# ESP32_FLASH_CARD_READER.net
KiCad netlist of a schematic drawn in Altium Designer
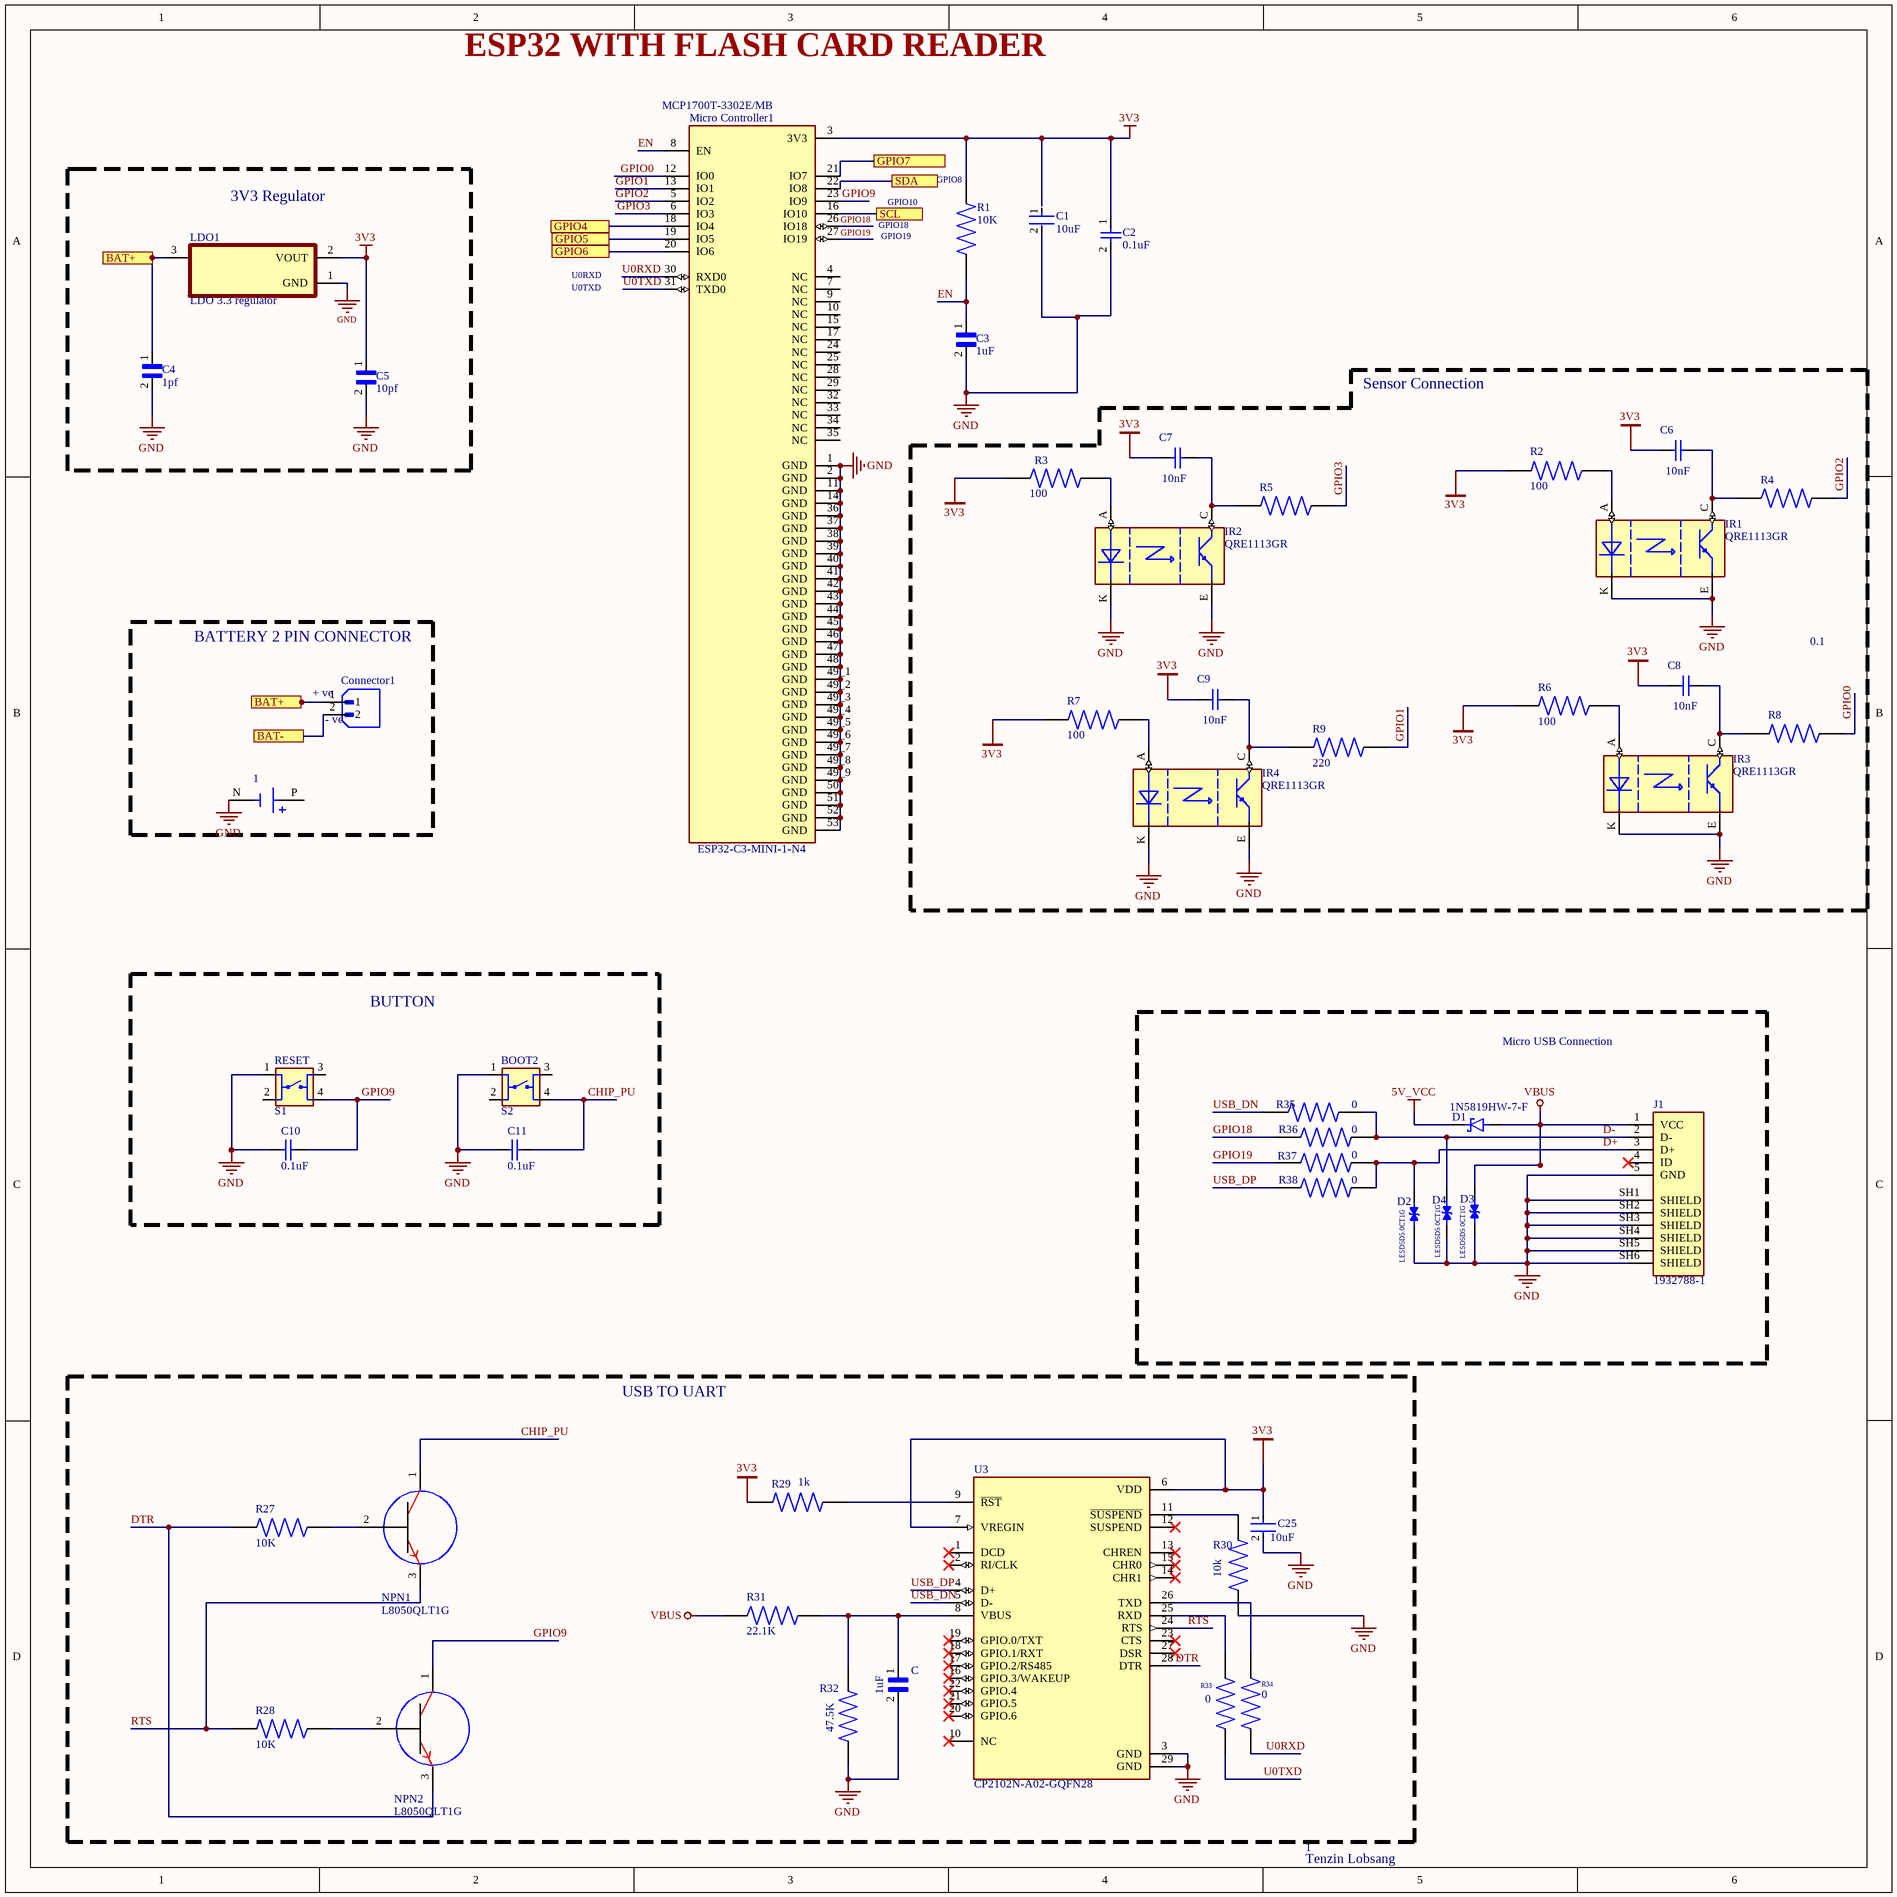
[diagram p0: ESP32_FLASH_CARD_READER.SchDoc]

(export (version "E")
  (design (tool "Eeschema 10.0.6"))
  (components
    (comp (ref "1")
      (value "~")
      (footprint "BAT_1043")
      (fields (field (name "MP") "1043"))
      (libsource (lib "1043") (part "1043"))
    )
    (comp (ref "BOOT2")
      (value "S2")
      (footprint "SW_4-1437565-2")
      (description "Switch Tactile OFF (ON) SPST Round Button Gull Wing 0.05A 12VDC 1.57N SMD T/R")
      (fields (field (name "MP") "4-1437565-2"))
      (libsource (lib "Switch_button") (part "4-1437565-2"))
    )
    (comp (ref "C")
      (value "1uF")
      (footprint "CAPC1608X90N")
      (description "1ÂµF Â±10% 16V Ceramic Capacitor X7R 0603 (1608 Metric)")
      (fields (field (name "DIGI-KEY_PART_NUMBER") "1276-1019-1-ND") (field (name "MP") "CL10B105KO8NNNC"))
      (libsource (lib "CAP_1uF") (part "CL10B105KO8NNNC"))
    )
    (comp (ref "C1")
      (value "10uF")
      (footprint "CAPC2012X88N")
      (description "Cap Ceramic 10uF 25V X5R ±20% Pad SMD 0603 +85°C T/R")
      (fields (field (name "TOLERANCE") "20%"))
      (libsource (lib "CAP 10 uF") (part "CMP-13271-004224-1"))
    )
    (comp (ref "C2")
      (value "0.1uF")
      (footprint "CAPC1608X90X35NL10T15")
      (description "Chip Capacitor, 0.1 uF, +/- 10%, 50 V, -55 to 125 degC, 0603 (1608 Metric), RoHS, Tape and Reel")
      (fields (field (name "TOLERANCE") "10%") (field (name "VOLTAGE") "50V"))
      (libsource (lib "") (part "CMP-2100-03643-1_1"))
    )
    (comp (ref "C3")
      (value "1uF")
      (footprint "CAPC1608X90N")
      (description "1ÂµF Â±10% 16V Ceramic Capacitor X7R 0603 (1608 Metric)")
      (fields (field (name "DIGI-KEY_PART_NUMBER") "1276-1019-1-ND") (field (name "MP") "CL10B105KO8NNNC"))
      (libsource (lib "CAP_1uF") (part "CL10B105KO8NNNC"))
    )
    (comp (ref "C4")
      (value "1pf")
      (footprint "CAPC2012X88N")
      (fields (field (name "MP") "C0805C100K5RAC7800"))
      (libsource (lib "C0805C100K5RAC7800") (part "C0805C100K5RAC7800"))
    )
    (comp (ref "C5")
      (value "10pf")
      (footprint "CAPC2012X88N")
      (fields (field (name "MP") "C0805C100K5RAC7800"))
      (libsource (lib "C0805C100K5RAC7800") (part "C0805C100K5RAC7800"))
    )
    (comp (ref "C6")
      (value "10nF")
      (footprint "WCAP-CSGP_0805_L2W1.25H1.25")
      (description "WCAP-CSGP Multilayer Ceramic Chip Capacitor, General Purpose, size 0805, NP0, 10nF, 10V")
      (fields
        (field (name "MANUFACTURER PART NUMBER") "885012007009")
        (field (name "MANUFACTURER") "Wurth Elektronik")
      )
      (libsource (lib "10nf_CAP_WCAP-CSGP") (part "885012007009"))
    )
    (comp (ref "C7")
      (value "10nF")
      (footprint "WCAP-CSGP_0805_L2W1.25H1.25")
      (description "WCAP-CSGP Multilayer Ceramic Chip Capacitor, General Purpose, size 0805, NP0, 10nF, 10V")
      (fields
        (field (name "MANUFACTURER PART NUMBER") "885012007009")
        (field (name "MANUFACTURER") "Wurth Elektronik")
      )
      (libsource (lib "10nf_CAP_WCAP-CSGP") (part "885012007009"))
    )
    (comp (ref "C8")
      (value "10nF")
      (footprint "WCAP-CSGP_0805_L2W1.25H1.25")
      (description "WCAP-CSGP Multilayer Ceramic Chip Capacitor, General Purpose, size 0805, NP0, 10nF, 10V")
      (fields
        (field (name "MANUFACTURER PART NUMBER") "885012007009")
        (field (name "MANUFACTURER") "Wurth Elektronik")
      )
      (libsource (lib "10nf_CAP_WCAP-CSGP") (part "885012007009"))
    )
    (comp (ref "C9")
      (value "10nF")
      (footprint "WCAP-CSGP_0805_L2W1.25H1.25")
      (description "WCAP-CSGP Multilayer Ceramic Chip Capacitor, General Purpose, size 0805, NP0, 10nF, 10V")
      (fields
        (field (name "MANUFACTURER PART NUMBER") "885012007009")
        (field (name "MANUFACTURER") "Wurth Elektronik")
      )
      (libsource (lib "10nf_CAP_WCAP-CSGP") (part "885012007009"))
    )
    (comp (ref "C10")
      (value "0.1uF")
      (footprint "CAPC1608X90X35NL10T15")
      (description "Chip Capacitor, 0.1 uF, +/- 10%, 50 V, -55 to 125 degC, 0603 (1608 Metric), RoHS, Tape and Reel")
      (fields (field (name "TOLERANCE") "10%") (field (name "VOLTAGE") "50V"))
      (libsource (lib "CAP 0.1uF") (part "CMP-2100-03643-1"))
    )
    (comp (ref "C11")
      (value "0.1uF")
      (footprint "CAPC1608X90X35NL10T15")
      (description "Chip Capacitor, 0.1 uF, +/- 10%, 50 V, -55 to 125 degC, 0603 (1608 Metric), RoHS, Tape and Reel")
      (fields (field (name "TOLERANCE") "10%") (field (name "VOLTAGE") "50V"))
      (libsource (lib "CAP 0.1uF") (part "CMP-2100-03643-1"))
    )
    (comp (ref "C25")
      (value "10uF")
      (footprint "CAPC2012X88N")
      (description "Cap Ceramic 10uF 25V X5R ±20% Pad SMD 0603 +85°C T/R")
      (fields (field (name "TOLERANCE") "20%"))
      (libsource (lib "CAP 10 uF") (part "CMP-13271-004224-1"))
    )
    (comp (ref "Connector1")
      (value "B2B-XH-A")
      (footprint "JST_B2B-XH-A")
      (fields (field (name "MF") "{'manufacturer': u'JST Sales America Inc.'}"))
      (libsource (lib "2_pin_connector_B2B-XH-A") (part "B2B-XH-A"))
    )
    (comp (ref "D1")
      (value "1N5819HW-7-F")
      (footprint "SOD3715X145N")
      (description "Diode Schottky 40 V 1A Surface Mount SOD-123")
      (fields (field (name "MF") "Diodes Inc."))
      (libsource (lib "D1_1N589HW-7-F") (part "1N5819HW-7-F"))
    )
    (comp (ref "D2")
      (value "LESD5D5.0CT1G")
      (footprint "TVS_LESD5D5.0CT1G")
      (description "Transient Voltage Suppressors for ESD Protection")
      (fields (field (name "MF") "Leshan Radio Co."))
      (libsource (lib "D2_LESD5_OCTR1G") (part "LESD5D5.0CT1G"))
    )
    (comp (ref "D3")
      (value "LESD5D5.0CT1G")
      (footprint "TVS_LESD5D5.0CT1G")
      (description "Transient Voltage Suppressors for ESD Protection")
      (fields (field (name "MF") "Leshan Radio Co."))
      (libsource (lib "D2_LESD5_OCTR1G") (part "LESD5D5.0CT1G"))
    )
    (comp (ref "D4")
      (value "LESD5D5.0CT1G")
      (footprint "TVS_LESD5D5.0CT1G")
      (description "Transient Voltage Suppressors for ESD Protection")
      (fields (field (name "MF") "Leshan Radio Co."))
      (libsource (lib "D2_LESD5_OCTR1G") (part "LESD5D5.0CT1G"))
    )
    (comp (ref "IR1")
      (value "QRE1113GR")
      (footprint "4LEADSMD")
      (description "Optical Switches, Reflective, Phototransistor Output Reflective Sensor")
      (fields (field (name "MF") "SparkFun") (field (name "MP") "QRE1113"))
      (libsource (lib "QRE1113GR") (part "QRE1113GR"))
    )
    (comp (ref "IR2")
      (value "QRE1113GR")
      (footprint "4LEADSMD")
      (description "Optical Switches, Reflective, Phototransistor Output Reflective Sensor")
      (fields (field (name "MF") "SparkFun") (field (name "MP") "QRE1113"))
      (libsource (lib "QRE1113GR") (part "QRE1113GR"))
    )
    (comp (ref "IR3")
      (value "QRE1113GR")
      (footprint "4LEADSMD")
      (description "Optical Switches, Reflective, Phototransistor Output Reflective Sensor")
      (fields (field (name "MF") "SparkFun") (field (name "MP") "QRE1113"))
      (libsource (lib "QRE1113GR") (part "QRE1113GR"))
    )
    (comp (ref "IR4")
      (value "QRE1113GR")
      (footprint "4LEADSMD")
      (description "Optical Switches, Reflective, Phototransistor Output Reflective Sensor")
      (fields (field (name "MF") "SparkFun") (field (name "MP") "QRE1113"))
      (libsource (lib "QRE1113GR") (part "QRE1113GR"))
    )
    (comp (ref "J1")
      (value "1932788-1")
      (footprint "TE_1932788-1")
      (libsource (lib "Micro_USB") (part "1932788-1"))
    )
    (comp (ref "LDO1")
      (value "LDO 3.3 regulator")
      (footprint "SOT95P237X112-3N")
      (description "25V 10uF X5R ±20% 0603 Multilayer Ceramic Capacitors MLCC - SMD/SMT ROHS")
      (fields (field (name "MP") "MCP1700T-3002E/TT") (field (name "MF") "Microchip"))
      (libsource (lib "Flash_Card_Reader_1") (part "MCP1700T-3002E/TT"))
    )
    (comp (ref "Micro Controller1")
      (value "ESP32-C3-MINI-1-N4")
      (footprint "XCVR_ESP32-C3-MINI-1-N4")
      (description "Pwr Sply Func, Voltage Regulator, LDO, SOT-89, PD 1.635W, VO 3.3V, Regline +/-0.75%/V")
      (fields
        (field (name "MF") "Espressif Systems")
        (field (name "SUPPLIER PART NUMBER 1") "MCP1700T-3302E/MB")
        (field (name "MANUFACTURER") "Microchip")
      )
      (libsource (lib "ESP32-C3-MINI-1-N4") (part "ESP32-C3-MINI-1-N4"))
    )
    (comp (ref "NPN1")
      (value "L8050QLT1G")
      (footprint "SOT-23")
      (libsource (lib "Transistor") (part "L8050QLT1G"))
    )
    (comp (ref "NPN2")
      (value "L8050QLT1G")
      (footprint "SOT-23")
      (libsource (lib "Transistor") (part "L8050QLT1G"))
    )
    (comp (ref "R1")
      (value "10K")
      (footprint "RESC1005X40N")
      (description "CRG0402 chip resistor,10K 5% 0.063W ¦ TE Connectivity CRG0402J10K/10")
      (fields (field (name "MF") "TE Connectivity") (field (name "MP") "CRG0402J10K/10"))
      (libsource (lib "10K_CRG0402J10K_10") (part "CRG0402J10K/10"))
    )
    (comp (ref "R2")
      (value "100")
      (footprint "RESC6432X75N")
      (description "CRS Series Anti-surge Resistor 2512 Case 100Ohms 2W +/-100ppm/degC ¦ Bourns CRS2512-FX-1000ELF")
      (fields (field (name "MF") "Bourns") (field (name "MP") "CRS2512-FX-1000ELF"))
      (libsource (lib "100ohh") (part "CRS2512-FX-1000ELF"))
    )
    (comp (ref "R3")
      (value "100")
      (footprint "RESC6432X75N")
      (description "CRS Series Anti-surge Resistor 2512 Case 100Ohms 2W +/-100ppm/degC ¦ Bourns CRS2512-FX-1000ELF")
      (fields (field (name "MF") "Bourns") (field (name "MP") "CRS2512-FX-1000ELF"))
      (libsource (lib "100ohh") (part "CRS2512-FX-1000ELF"))
    )
    (comp (ref "R4")
      (value "220")
      (footprint "RESC1005X35N")
      (fields
        (field (name "MF") "TE Connectivity")
        (field (name "MP") "CPF0402B220RE1")
        (field (name "TOLERANCE") ".1%")
      )
      (libsource (lib "220_ohm_CPF0402B220RE1") (part "CPF0402B220RE1"))
    )
    (comp (ref "R5")
      (value "220")
      (footprint "RESC1005X35N")
      (fields
        (field (name "MF") "TE Connectivity")
        (field (name "MP") "CPF0402B220RE1")
        (field (name "TOLERANCE") ".1%")
      )
      (libsource (lib "220_ohm_CPF0402B220RE1") (part "CPF0402B220RE1"))
    )
    (comp (ref "R6")
      (value "100")
      (footprint "RESC6432X75N")
      (description "CRS Series Anti-surge Resistor 2512 Case 100Ohms 2W +/-100ppm/degC ¦ Bourns CRS2512-FX-1000ELF")
      (fields (field (name "MF") "Bourns") (field (name "MP") "CRS2512-FX-1000ELF"))
      (libsource (lib "100ohh") (part "CRS2512-FX-1000ELF"))
    )
    (comp (ref "R7")
      (value "100")
      (footprint "RESC6432X75N")
      (description "CRS Series Anti-surge Resistor 2512 Case 100Ohms 2W +/-100ppm/degC ¦ Bourns CRS2512-FX-1000ELF")
      (fields (field (name "MF") "Bourns") (field (name "MP") "CRS2512-FX-1000ELF"))
      (libsource (lib "100ohh") (part "CRS2512-FX-1000ELF"))
    )
    (comp (ref "R8")
      (value "220")
      (footprint "RESC1005X35N")
      (fields
        (field (name "MF") "TE Connectivity")
        (field (name "MP") "CPF0402B220RE1")
        (field (name "TOLERANCE") ".1%")
      )
      (libsource (lib "220_ohm_CPF0402B220RE1") (part "CPF0402B220RE1"))
    )
    (comp (ref "R9")
      (value "220")
      (footprint "RESC1005X35N")
      (fields
        (field (name "MF") "TE Connectivity")
        (field (name "MP") "CPF0402B220RE1")
        (field (name "TOLERANCE") ".1%")
      )
      (libsource (lib "220_ohm_CPF0402B220RE1") (part "CPF0402B220RE1"))
    )
    (comp (ref "R27")
      (value "10K")
      (footprint "RESC1005X40N")
      (description "CRG0402 chip resistor,10K 5% 0.063W ¦ TE Connectivity CRG0402J10K/10")
      (fields (field (name "MF") "TE Connectivity") (field (name "MP") "CRG0402J10K/10"))
      (libsource (lib "10K_CRG0402J10K_10") (part "CRG0402J10K/10"))
    )
    (comp (ref "R28")
      (value "10K")
      (footprint "RESC1005X40N")
      (description "CRG0402 chip resistor,10K 5% 0.063W ¦ TE Connectivity CRG0402J10K/10")
      (fields (field (name "MF") "TE Connectivity") (field (name "MP") "CRG0402J10K/10"))
      (libsource (lib "10K_CRG0402J10K_10") (part "CRG0402J10K/10"))
    )
    (comp (ref "R29")
      (value "1k")
      (footprint "RES_ERJU06F1001V")
      (description "Res Thick Film 0805 1K Ohm 1% 0.125W(1/8W) Â±100ppm/C Sulfur Resistant Pad SMD Automotive T/R")
      (fields (field (name "MF") "Panasonic") (field (name "MP") "ERJU06F1001V"))
      (libsource (lib "1K_ohm_resistor") (part "ERJU06F1001V"))
    )
    (comp (ref "R30")
      (value "10k")
      (footprint "RESC1005X40N")
      (description "CRG0402 chip resistor,10K 5% 0.063W ¦ TE Connectivity CRG0402J10K/10")
      (fields (field (name "MF") "TE Connectivity") (field (name "MP") "CRG0402J10K/10"))
      (libsource (lib "10K_CRG0402J10K_10") (part "CRG0402J10K/10"))
    )
    (comp (ref "R31")
      (value "22.1K")
      (footprint "RES_ERJS02F2212X")
      (fields (field (name "MP") "ERJS02F2212X"))
      (libsource (lib "22_1K_Resistor") (part "ERJS02F2212X"))
    )
    (comp (ref "R32")
      (value "47.5K")
      (footprint "RES_ERJU06F4752V")
      (fields (field (name "MP") "ERJU06F4752V"))
      (libsource (lib "44-5-k_ohm_resistor") (part "ERJU06F4752V"))
    )
    (comp (ref "R33")
      (value "0")
      (footprint "RESC1608X55N")
      (fields (field (name "MP") "MC0603SAF0000T5E"))
      (libsource (lib "0_ohm_resistor") (part "MC0603SAF0000T5E"))
    )
    (comp (ref "R34")
      (value "0")
      (footprint "RESC1608X55N")
      (fields (field (name "MP") "MC0603SAF0000T5E"))
      (libsource (lib "0_ohm_resistor") (part "MC0603SAF0000T5E"))
    )
    (comp (ref "R35")
      (value "0")
      (footprint "RESC1608X55N")
      (fields (field (name "MP") "MC0603SAF0000T5E"))
      (libsource (lib "0_ohm_resistor") (part "MC0603SAF0000T5E"))
    )
    (comp (ref "R36")
      (value "0")
      (footprint "RESC1608X55N")
      (fields (field (name "MP") "MC0603SAF0000T5E"))
      (libsource (lib "0_ohm_resistor") (part "MC0603SAF0000T5E"))
    )
    (comp (ref "R37")
      (value "0")
      (footprint "RESC1608X55N")
      (fields (field (name "MP") "MC0603SAF0000T5E"))
      (libsource (lib "0_ohm_resistor") (part "MC0603SAF0000T5E"))
    )
    (comp (ref "R38")
      (value "0")
      (footprint "RESC1608X55N")
      (fields (field (name "MP") "MC0603SAF0000T5E"))
      (libsource (lib "0_ohm_resistor") (part "MC0603SAF0000T5E"))
    )
    (comp (ref "RESET")
      (value "S1")
      (footprint "SW_4-1437565-2")
      (description "Switch Tactile OFF (ON) SPST Round Button Gull Wing 0.05A 12VDC 1.57N SMD T/R")
      (fields (field (name "MP") "4-1437565-2"))
      (libsource (lib "Switch_button") (part "4-1437565-2"))
    )
    (comp (ref "U3")
      (value "CP2102N-A02-GQFN28")
      (footprint "QFN50P500X500X80-29N")
      (description "USB Bridge, USB to UART USB 2.0 UART Interface 28-QFN (5x5)")
      (fields (field (name "MF") "Silicon Labs"))
      (libsource (lib "USB-to-UART") (part "CP2102N-A02-GQFN28"))
    )
  )
  (nets
    (net (code "1") (name "/BAT+") (class "Default")
      (node (ref "C4") (pin "1") (pinfunction "1_1") (pintype "passive"))
      (node (ref "Connector1") (pin "1") (pinfunction "1_1") (pintype "passive"))
      (node (ref "LDO1") (pin "3") (pinfunction "VIN_3") (pintype "passive"))
    )
    (net (code "2") (name "/BAT-") (class "Default")
      (node (ref "Connector1") (pin "2") (pinfunction "2_2") (pintype "passive"))
    )
    (net (code "3") (name "/CHIP_PU") (class "Default")
      (node (ref "BOOT2") (pin "4") (pinfunction "4_4") (pintype "passive"))
      (node (ref "C11") (pin "2") (pinfunction "2_2") (pintype "passive"))
      (node (ref "NPN1") (pin "1") (pinfunction "1_1") (pintype "passive"))
    )
    (net (code "4") (name "/D+") (class "Default")
      (node (ref "D2") (pin "2") (pinfunction "2_2") (pintype "passive"))
      (node (ref "J1") (pin "3") (pinfunction "D+_3") (pintype "passive"))
      (node (ref "R37") (pin "1") (pinfunction "1_1") (pintype "passive"))
      (node (ref "R38") (pin "1") (pinfunction "1_1") (pintype "passive"))
    )
    (net (code "5") (name "/D-") (class "Default")
      (node (ref "D4") (pin "2") (pinfunction "2_2") (pintype "passive"))
      (node (ref "J1") (pin "2") (pinfunction "D-_2") (pintype "passive"))
      (node (ref "R35") (pin "1") (pinfunction "1_1") (pintype "passive"))
      (node (ref "R36") (pin "1") (pinfunction "1_1") (pintype "passive"))
    )
    (net (code "6") (name "/DTR") (class "Default")
      (node (ref "R27") (pin "1") (pinfunction "1_1") (pintype "passive"))
      (node (ref "U3") (pin "28") (pinfunction "DTR_28") (pintype "passive"))
    )
    (net (code "7") (name "/EN") (class "Default")
      (node (ref "C3") (pin "1") (pinfunction "1_1") (pintype "passive"))
      (node (ref "Micro Controller1") (pin "8") (pinfunction "EN_8") (pintype "passive"))
      (node (ref "R1") (pin "1") (pinfunction "1_1") (pintype "passive"))
    )
    (net (code "8") (name "/GPIO0") (class "Default")
      (node (ref "Micro Controller1") (pin "12") (pinfunction "IO0_12") (pintype "passive"))
      (node (ref "R8") (pin "2") (pinfunction "2_2") (pintype "passive"))
    )
    (net (code "9") (name "/GPIO1") (class "Default")
      (node (ref "Micro Controller1") (pin "13") (pinfunction "IO1_13") (pintype "passive"))
      (node (ref "R9") (pin "2") (pinfunction "2_2") (pintype "passive"))
    )
    (net (code "10") (name "/GPIO2") (class "Default")
      (node (ref "Micro Controller1") (pin "5") (pinfunction "IO2_5") (pintype "passive"))
      (node (ref "R4") (pin "2") (pinfunction "2_2") (pintype "passive"))
    )
    (net (code "11") (name "/GPIO3") (class "Default")
      (node (ref "Micro Controller1") (pin "6") (pinfunction "IO3_6") (pintype "passive"))
      (node (ref "R5") (pin "2") (pinfunction "2_2") (pintype "passive"))
    )
    (net (code "12") (name "/GPIO4") (class "Default")
      (node (ref "Micro Controller1") (pin "18") (pinfunction "IO4_18") (pintype "passive"))
    )
    (net (code "13") (name "/GPIO5") (class "Default")
      (node (ref "Micro Controller1") (pin "19") (pinfunction "IO5_19") (pintype "passive"))
    )
    (net (code "14") (name "/GPIO6") (class "Default")
      (node (ref "Micro Controller1") (pin "20") (pinfunction "IO6_20") (pintype "passive"))
    )
    (net (code "15") (name "/GPIO7") (class "Default")
      (node (ref "Micro Controller1") (pin "21") (pinfunction "IO7_21") (pintype "passive"))
    )
    (net (code "16") (name "/GPIO9") (class "Default")
      (node (ref "C10") (pin "2") (pinfunction "2_2") (pintype "passive"))
      (node (ref "Micro Controller1") (pin "23") (pinfunction "IO9_23") (pintype "passive"))
      (node (ref "NPN2") (pin "1") (pinfunction "1_1") (pintype "passive"))
      (node (ref "RESET") (pin "4") (pinfunction "4_4") (pintype "passive"))
    )
    (net (code "17") (name "/GPIO18") (class "Default")
      (node (ref "Micro Controller1") (pin "26") (pinfunction "IO18_26") (pintype "bidirectional"))
      (node (ref "R36") (pin "2") (pinfunction "2_2") (pintype "passive"))
    )
    (net (code "18") (name "/GPIO19") (class "Default")
      (node (ref "Micro Controller1") (pin "27") (pinfunction "IO19_27") (pintype "bidirectional"))
      (node (ref "R37") (pin "2") (pinfunction "2_2") (pintype "passive"))
    )
    (net (code "19") (name "/RTS") (class "Default")
      (node (ref "R28") (pin "1") (pinfunction "1_1") (pintype "passive"))
      (node (ref "U3") (pin "24") (pinfunction "RTS_24") (pintype "output"))
    )
    (net (code "20") (name "/SCL") (class "Default")
      (node (ref "Micro Controller1") (pin "16") (pinfunction "IO10_16") (pintype "passive"))
    )
    (net (code "21") (name "/SDA") (class "Default")
      (node (ref "Micro Controller1") (pin "22") (pinfunction "IO8_22") (pintype "passive"))
    )
    (net (code "22") (name "/U0RXD") (class "Default")
      (node (ref "Micro Controller1") (pin "30") (pinfunction "RXD0_30") (pintype "bidirectional"))
      (node (ref "R34") (pin "1") (pinfunction "1_1") (pintype "passive"))
    )
    (net (code "23") (name "/U0TXD") (class "Default")
      (node (ref "Micro Controller1") (pin "31") (pinfunction "TXD0_31") (pintype "bidirectional"))
      (node (ref "R33") (pin "1") (pinfunction "1_1") (pintype "passive"))
    )
    (net (code "24") (name "/USB_DN") (class "Default")
      (node (ref "R35") (pin "2") (pinfunction "2_2") (pintype "passive"))
      (node (ref "U3") (pin "5") (pinfunction "D-_5") (pintype "bidirectional"))
    )
    (net (code "25") (name "/USB_DP") (class "Default")
      (node (ref "R38") (pin "2") (pinfunction "2_2") (pintype "passive"))
      (node (ref "U3") (pin "4") (pinfunction "D+_4") (pintype "bidirectional"))
    )
    (net (code "26") (name "3V3") (class "Default")
      (node (ref "C2") (pin "1") (pinfunction "1_1") (pintype "passive"))
      (node (ref "C25") (pin "1") (pinfunction "1_1") (pintype "passive"))
      (node (ref "C5") (pin "1") (pinfunction "1_1") (pintype "passive"))
      (node (ref "C6") (pin "1") (pinfunction "1_1") (pintype "passive"))
      (node (ref "C7") (pin "1") (pinfunction "1_1") (pintype "passive"))
      (node (ref "C8") (pin "1") (pinfunction "1_1") (pintype "passive"))
      (node (ref "C9") (pin "1") (pinfunction "1_1") (pintype "passive"))
      (node (ref "LDO1") (pin "2") (pinfunction "VOUT_2") (pintype "power_in"))
      (node (ref "Micro Controller1") (pin "3") (pinfunction "3V3_3") (pintype "passive"))
      (node (ref "R1") (pin "2") (pinfunction "2_2") (pintype "passive"))
      (node (ref "R2") (pin "1") (pinfunction "1_1") (pintype "passive"))
      (node (ref "R29") (pin "1") (pinfunction "1_1") (pintype "passive"))
      (node (ref "R3") (pin "1") (pinfunction "1_1") (pintype "passive"))
      (node (ref "R6") (pin "1") (pinfunction "1_1") (pintype "passive"))
      (node (ref "R7") (pin "1") (pinfunction "1_1") (pintype "passive"))
      (node (ref "U3") (pin "6") (pinfunction "VDD_6") (pintype "power_in"))
      (node (ref "U3") (pin "7") (pinfunction "VREGIN_7") (pintype "input"))
    )
    (net (code "27") (name "5V_VCC") (class "Default")
      (node (ref "D1") (pin "C") (pinfunction "K_C") (pintype "passive"))
    )
    (net (code "28") (name "GND") (class "Default")
      (node (ref "1") (pin "N") (pinfunction "NEG_N") (pintype "passive"))
      (node (ref "BOOT2") (pin "1") (pinfunction "1_1") (pintype "passive"))
      (node (ref "C") (pin "2") (pinfunction "2_2") (pintype "passive"))
      (node (ref "C1") (pin "2") (pinfunction "2_2") (pintype "passive"))
      (node (ref "C10") (pin "1") (pinfunction "1_1") (pintype "passive"))
      (node (ref "C11") (pin "1") (pinfunction "1_1") (pintype "passive"))
      (node (ref "C2") (pin "2") (pinfunction "2_2") (pintype "passive"))
      (node (ref "C25") (pin "2") (pinfunction "2_2") (pintype "passive"))
      (node (ref "C3") (pin "2") (pinfunction "2_2") (pintype "passive"))
      (node (ref "C4") (pin "2") (pinfunction "2_2") (pintype "passive"))
      (node (ref "C5") (pin "2") (pinfunction "2_2") (pintype "passive"))
      (node (ref "D2") (pin "1") (pinfunction "1_1") (pintype "passive"))
      (node (ref "D3") (pin "2") (pinfunction "2_2") (pintype "passive"))
      (node (ref "D4") (pin "1") (pinfunction "1_1") (pintype "passive"))
      (node (ref "IR1") (pin "E") (pinfunction "E_E") (pintype "passive"))
      (node (ref "IR1") (pin "K") (pinfunction "K_K") (pintype "passive"))
      (node (ref "IR2") (pin "E") (pinfunction "E_E") (pintype "passive"))
      (node (ref "IR2") (pin "K") (pinfunction "K_K") (pintype "passive"))
      (node (ref "IR3") (pin "E") (pinfunction "E_E") (pintype "passive"))
      (node (ref "IR3") (pin "K") (pinfunction "K_K") (pintype "passive"))
      (node (ref "IR4") (pin "E") (pinfunction "E_E") (pintype "passive"))
      (node (ref "IR4") (pin "K") (pinfunction "K_K") (pintype "passive"))
      (node (ref "J1") (pin "5") (pinfunction "GND_5") (pintype "passive"))
      (node (ref "J1") (pin "SH1") (pinfunction "SHIELD_SH1") (pintype "passive"))
      (node (ref "J1") (pin "SH2") (pinfunction "SHIELD_SH2") (pintype "passive"))
      (node (ref "J1") (pin "SH3") (pinfunction "SHIELD_SH3") (pintype "passive"))
      (node (ref "J1") (pin "SH4") (pinfunction "SHIELD_SH4") (pintype "passive"))
      (node (ref "J1") (pin "SH5") (pinfunction "SHIELD_SH5") (pintype "passive"))
      (node (ref "J1") (pin "SH6") (pinfunction "SHIELD_SH6") (pintype "passive"))
      (node (ref "LDO1") (pin "1") (pinfunction "GND_1") (pintype "passive"))
      (node (ref "Micro Controller1") (pin "1") (pinfunction "GND_1") (pintype "passive"))
      (node (ref "Micro Controller1") (pin "11") (pinfunction "GND_11") (pintype "passive"))
      (node (ref "Micro Controller1") (pin "14") (pinfunction "GND_14") (pintype "passive"))
      (node (ref "Micro Controller1") (pin "2") (pinfunction "GND_2") (pintype "passive"))
      (node (ref "Micro Controller1") (pin "36") (pinfunction "GND_36") (pintype "passive"))
      (node (ref "Micro Controller1") (pin "37") (pinfunction "GND_37") (pintype "passive"))
      (node (ref "Micro Controller1") (pin "38") (pinfunction "GND_38") (pintype "passive"))
      (node (ref "Micro Controller1") (pin "39") (pinfunction "GND_39") (pintype "passive"))
      (node (ref "Micro Controller1") (pin "40") (pinfunction "GND_40") (pintype "passive"))
      (node (ref "Micro Controller1") (pin "41") (pinfunction "GND_41") (pintype "passive"))
      (node (ref "Micro Controller1") (pin "42") (pinfunction "GND_42") (pintype "passive"))
      (node (ref "Micro Controller1") (pin "43") (pinfunction "GND_43") (pintype "passive"))
      (node (ref "Micro Controller1") (pin "44") (pinfunction "GND_44") (pintype "passive"))
      (node (ref "Micro Controller1") (pin "45") (pinfunction "GND_45") (pintype "passive"))
      (node (ref "Micro Controller1") (pin "46") (pinfunction "GND_46") (pintype "passive"))
      (node (ref "Micro Controller1") (pin "47") (pinfunction "GND_47") (pintype "passive"))
      (node (ref "Micro Controller1") (pin "48") (pinfunction "GND_48") (pintype "passive"))
      (node (ref "Micro Controller1") (pin "49_1") (pinfunction "GND_49_1") (pintype "passive"))
      (node (ref "Micro Controller1") (pin "49_2") (pinfunction "GND_49_2") (pintype "passive"))
      (node (ref "Micro Controller1") (pin "49_3") (pinfunction "GND_49_3") (pintype "passive"))
      (node (ref "Micro Controller1") (pin "49_4") (pinfunction "GND_49_4") (pintype "passive"))
      (node (ref "Micro Controller1") (pin "49_5") (pinfunction "GND_49_5") (pintype "passive"))
      (node (ref "Micro Controller1") (pin "49_6") (pinfunction "GND_49_6") (pintype "passive"))
      (node (ref "Micro Controller1") (pin "49_7") (pinfunction "GND_49_7") (pintype "passive"))
      (node (ref "Micro Controller1") (pin "49_8") (pinfunction "GND_49_8") (pintype "passive"))
      (node (ref "Micro Controller1") (pin "49_9") (pinfunction "GND_49_9") (pintype "passive"))
      (node (ref "Micro Controller1") (pin "50") (pinfunction "GND_50") (pintype "passive"))
      (node (ref "Micro Controller1") (pin "51") (pinfunction "GND_51") (pintype "passive"))
      (node (ref "Micro Controller1") (pin "52") (pinfunction "GND_52") (pintype "passive"))
      (node (ref "Micro Controller1") (pin "53") (pinfunction "GND_53") (pintype "passive"))
      (node (ref "R30") (pin "1") (pinfunction "1_1") (pintype "passive"))
      (node (ref "R32") (pin "1") (pinfunction "1_1") (pintype "passive"))
      (node (ref "RESET") (pin "1") (pinfunction "1_1") (pintype "passive"))
      (node (ref "U3") (pin "29") (pinfunction "GND_29") (pintype "passive"))
      (node (ref "U3") (pin "3") (pinfunction "GND_3") (pintype "passive"))
    )
    (net (code "29") (name "Net-(C6-Pad2)") (class "Default")
      (node (ref "C6") (pin "2") (pinfunction "2_2") (pintype "passive"))
      (node (ref "IR1") (pin "C") (pinfunction "C_C") (pintype "bidirectional"))
      (node (ref "R4") (pin "1") (pinfunction "1_1") (pintype "passive"))
    )
    (net (code "30") (name "Net-(C7-Pad2)") (class "Default")
      (node (ref "C7") (pin "2") (pinfunction "2_2") (pintype "passive"))
      (node (ref "IR2") (pin "C") (pinfunction "C_C") (pintype "bidirectional"))
      (node (ref "R5") (pin "1") (pinfunction "1_1") (pintype "passive"))
    )
    (net (code "31") (name "Net-(C8-Pad2)") (class "Default")
      (node (ref "C8") (pin "2") (pinfunction "2_2") (pintype "passive"))
      (node (ref "IR3") (pin "C") (pinfunction "C_C") (pintype "bidirectional"))
      (node (ref "R8") (pin "1") (pinfunction "1_1") (pintype "passive"))
    )
    (net (code "32") (name "Net-(C9-Pad2)") (class "Default")
      (node (ref "C9") (pin "2") (pinfunction "2_2") (pintype "passive"))
      (node (ref "IR4") (pin "C") (pinfunction "C_C") (pintype "bidirectional"))
      (node (ref "R9") (pin "1") (pinfunction "1_1") (pintype "passive"))
    )
    (net (code "33") (name "Net-(IR1-PadA)") (class "Default")
      (node (ref "IR1") (pin "A") (pinfunction "A_A") (pintype "bidirectional"))
      (node (ref "R2") (pin "2") (pinfunction "2_2") (pintype "passive"))
    )
    (net (code "34") (name "Net-(IR2-PadA)") (class "Default")
      (node (ref "IR2") (pin "A") (pinfunction "A_A") (pintype "bidirectional"))
      (node (ref "R3") (pin "2") (pinfunction "2_2") (pintype "passive"))
    )
    (net (code "35") (name "Net-(IR3-PadA)") (class "Default")
      (node (ref "IR3") (pin "A") (pinfunction "A_A") (pintype "bidirectional"))
      (node (ref "R6") (pin "2") (pinfunction "2_2") (pintype "passive"))
    )
    (net (code "36") (name "Net-(IR4-PadA)") (class "Default")
      (node (ref "IR4") (pin "A") (pinfunction "A_A") (pintype "bidirectional"))
      (node (ref "R7") (pin "2") (pinfunction "2_2") (pintype "passive"))
    )
    (net (code "37") (name "Net-(NPN1-Pad2)") (class "Default")
      (node (ref "NPN1") (pin "2") (pinfunction "2_2") (pintype "passive"))
      (node (ref "R27") (pin "2") (pinfunction "2_2") (pintype "passive"))
    )
    (net (code "38") (name "Net-(NPN2-Pad2)") (class "Default")
      (node (ref "NPN2") (pin "2") (pinfunction "2_2") (pintype "passive"))
      (node (ref "R28") (pin "2") (pinfunction "2_2") (pintype "passive"))
    )
    (net (code "39") (name "Net-(U3-RXD)") (class "Default")
      (node (ref "R33") (pin "2") (pinfunction "2_2") (pintype "passive"))
      (node (ref "U3") (pin "25") (pinfunction "RXD_25") (pintype "passive"))
    )
    (net (code "40") (name "Net-(U3-TXD)") (class "Default")
      (node (ref "R34") (pin "2") (pinfunction "2_2") (pintype "passive"))
      (node (ref "U3") (pin "26") (pinfunction "TXD_26") (pintype "passive"))
    )
    (net (code "41") (name "Net-(U3-VBUS)") (class "Default")
      (node (ref "C") (pin "1") (pinfunction "1_1") (pintype "passive"))
      (node (ref "R31") (pin "2") (pinfunction "2_2") (pintype "passive"))
      (node (ref "R32") (pin "2") (pinfunction "2_2") (pintype "passive"))
      (node (ref "U3") (pin "8") (pinfunction "VBUS_8") (pintype "passive"))
    )
    (net (code "42") (name "Net-(U3-~{RST})") (class "Default")
      (node (ref "R29") (pin "2") (pinfunction "2_2") (pintype "passive"))
      (node (ref "U3") (pin "9") (pinfunction "~{RST}_9") (pintype "passive"))
    )
    (net (code "43") (name "Net-(U3-~{SUSPEND})") (class "Default")
      (node (ref "R30") (pin "2") (pinfunction "2_2") (pintype "passive"))
      (node (ref "U3") (pin "11") (pinfunction "~{SUSPEND}_11") (pintype "passive"))
    )
    (net (code "44") (name "VBUS") (class "Default")
      (node (ref "D1") (pin "A") (pinfunction "A_A") (pintype "passive"))
      (node (ref "D3") (pin "1") (pinfunction "1_1") (pintype "passive"))
      (node (ref "J1") (pin "1") (pinfunction "VCC_1") (pintype "power_in"))
      (node (ref "R31") (pin "1") (pinfunction "1_1") (pintype "passive"))
    )
    (net (code "45") (name "unconnected-(1-POS-PadP)") (class "Default")
      (node (ref "1") (pin "P") (pinfunction "POS_P") (pintype "passive"))
    )
    (net (code "46") (name "unconnected-(BOOT2-Pad2)") (class "Default")
      (node (ref "BOOT2") (pin "2") (pinfunction "2_2") (pintype "passive"))
    )
    (net (code "47") (name "unconnected-(BOOT2-Pad3)") (class "Default")
      (node (ref "BOOT2") (pin "3") (pinfunction "3_3") (pintype "passive"))
    )
    (net (code "48") (name "unconnected-(C1-Pad1)") (class "Default")
      (node (ref "C1") (pin "1") (pinfunction "1_1") (pintype "passive"))
    )
    (net (code "49") (name "unconnected-(J1-ID-Pad4)") (class "Default")
      (node (ref "J1") (pin "4") (pinfunction "ID_4") (pintype "passive+no_connect"))
    )
    (net (code "50") (name "unconnected-(Micro Controller1-NC-Pad4)") (class "Default")
      (node (ref "Micro Controller1") (pin "4") (pinfunction "NC_4") (pintype "passive"))
    )
    (net (code "51") (name "unconnected-(Micro Controller1-NC-Pad7)") (class "Default")
      (node (ref "Micro Controller1") (pin "7") (pinfunction "NC_7") (pintype "passive"))
    )
    (net (code "52") (name "unconnected-(Micro Controller1-NC-Pad9)") (class "Default")
      (node (ref "Micro Controller1") (pin "9") (pinfunction "NC_9") (pintype "passive"))
    )
    (net (code "53") (name "unconnected-(Micro Controller1-NC-Pad10)") (class "Default")
      (node (ref "Micro Controller1") (pin "10") (pinfunction "NC_10") (pintype "passive"))
    )
    (net (code "54") (name "unconnected-(Micro Controller1-NC-Pad15)") (class "Default")
      (node (ref "Micro Controller1") (pin "15") (pinfunction "NC_15") (pintype "passive"))
    )
    (net (code "55") (name "unconnected-(Micro Controller1-NC-Pad17)") (class "Default")
      (node (ref "Micro Controller1") (pin "17") (pinfunction "NC_17") (pintype "passive"))
    )
    (net (code "56") (name "unconnected-(Micro Controller1-NC-Pad24)") (class "Default")
      (node (ref "Micro Controller1") (pin "24") (pinfunction "NC_24") (pintype "passive"))
    )
    (net (code "57") (name "unconnected-(Micro Controller1-NC-Pad25)") (class "Default")
      (node (ref "Micro Controller1") (pin "25") (pinfunction "NC_25") (pintype "passive"))
    )
    (net (code "58") (name "unconnected-(Micro Controller1-NC-Pad28)") (class "Default")
      (node (ref "Micro Controller1") (pin "28") (pinfunction "NC_28") (pintype "passive"))
    )
    (net (code "59") (name "unconnected-(Micro Controller1-NC-Pad29)") (class "Default")
      (node (ref "Micro Controller1") (pin "29") (pinfunction "NC_29") (pintype "passive"))
    )
    (net (code "60") (name "unconnected-(Micro Controller1-NC-Pad32)") (class "Default")
      (node (ref "Micro Controller1") (pin "32") (pinfunction "NC_32") (pintype "passive"))
    )
    (net (code "61") (name "unconnected-(Micro Controller1-NC-Pad33)") (class "Default")
      (node (ref "Micro Controller1") (pin "33") (pinfunction "NC_33") (pintype "passive"))
    )
    (net (code "62") (name "unconnected-(Micro Controller1-NC-Pad34)") (class "Default")
      (node (ref "Micro Controller1") (pin "34") (pinfunction "NC_34") (pintype "passive"))
    )
    (net (code "63") (name "unconnected-(Micro Controller1-NC-Pad35)") (class "Default")
      (node (ref "Micro Controller1") (pin "35") (pinfunction "NC_35") (pintype "passive"))
    )
    (net (code "64") (name "unconnected-(NPN1-Pad3)") (class "Default")
      (node (ref "NPN1") (pin "3") (pinfunction "3_3") (pintype "passive"))
    )
    (net (code "65") (name "unconnected-(NPN2-Pad3)") (class "Default")
      (node (ref "NPN2") (pin "3") (pinfunction "3_3") (pintype "passive"))
    )
    (net (code "66") (name "unconnected-(RESET-Pad2)") (class "Default")
      (node (ref "RESET") (pin "2") (pinfunction "2_2") (pintype "passive"))
    )
    (net (code "67") (name "unconnected-(RESET-Pad3)") (class "Default")
      (node (ref "RESET") (pin "3") (pinfunction "3_3") (pintype "passive"))
    )
    (net (code "68") (name "unconnected-(U3-CHR0-Pad15)") (class "Default")
      (node (ref "U3") (pin "15") (pinfunction "CHR0_15") (pintype "output+no_connect"))
    )
    (net (code "69") (name "unconnected-(U3-CHR1-Pad14)") (class "Default")
      (node (ref "U3") (pin "14") (pinfunction "CHR1_14") (pintype "output+no_connect"))
    )
    (net (code "70") (name "unconnected-(U3-CHREN-Pad13)") (class "Default")
      (node (ref "U3") (pin "13") (pinfunction "CHREN_13") (pintype "passive+no_connect"))
    )
    (net (code "71") (name "unconnected-(U3-CTS-Pad23)") (class "Default")
      (node (ref "U3") (pin "23") (pinfunction "CTS_23") (pintype "passive+no_connect"))
    )
    (net (code "72") (name "unconnected-(U3-DCD-Pad1)") (class "Default")
      (node (ref "U3") (pin "1") (pinfunction "DCD_1") (pintype "passive+no_connect"))
    )
    (net (code "73") (name "unconnected-(U3-DSR-Pad27)") (class "Default")
      (node (ref "U3") (pin "27") (pinfunction "DSR_27") (pintype "passive+no_connect"))
    )
    (net (code "74") (name "unconnected-(U3-GPIO.0{slash}TXT-Pad19)") (class "Default")
      (node (ref "U3") (pin "19") (pinfunction "GPIO.0/TXT_19") (pintype "bidirectional+no_connect"))
    )
    (net (code "75") (name "unconnected-(U3-GPIO.1{slash}RXT-Pad18)") (class "Default")
      (node (ref "U3") (pin "18") (pinfunction "GPIO.1/RXT_18") (pintype "bidirectional+no_connect"))
    )
    (net (code "76") (name "unconnected-(U3-GPIO.2{slash}RS485-Pad17)") (class "Default")
      (node (ref "U3") (pin "17") (pinfunction "GPIO.2/RS485_17") (pintype "bidirectional+no_connect"))
    )
    (net (code "77") (name "unconnected-(U3-GPIO.3{slash}WAKEUP-Pad16)") (class "Default")
      (node (ref "U3") (pin "16") (pinfunction "GPIO.3/WAKEUP_16") (pintype "bidirectional+no_connect"))
    )
    (net (code "78") (name "unconnected-(U3-GPIO.4-Pad22)") (class "Default")
      (node (ref "U3") (pin "22") (pinfunction "GPIO.4_22") (pintype "bidirectional+no_connect"))
    )
    (net (code "79") (name "unconnected-(U3-GPIO.5-Pad21)") (class "Default")
      (node (ref "U3") (pin "21") (pinfunction "GPIO.5_21") (pintype "bidirectional+no_connect"))
    )
    (net (code "80") (name "unconnected-(U3-GPIO.6-Pad20)") (class "Default")
      (node (ref "U3") (pin "20") (pinfunction "GPIO.6_20") (pintype "bidirectional+no_connect"))
    )
    (net (code "81") (name "unconnected-(U3-NC-Pad10)") (class "Default")
      (node (ref "U3") (pin "10") (pinfunction "NC_10") (pintype "passive+no_connect"))
    )
    (net (code "82") (name "unconnected-(U3-RI{slash}CLK-Pad2)") (class "Default")
      (node (ref "U3") (pin "2") (pinfunction "RI/CLK_2") (pintype "bidirectional+no_connect"))
    )
    (net (code "83") (name "unconnected-(U3-SUSPEND-Pad12)") (class "Default")
      (node (ref "U3") (pin "12") (pinfunction "SUSPEND_12") (pintype "passive+no_connect"))
    )
  )
)
